# SD.net
KiCad netlist of a schematic drawn in Altium Designer
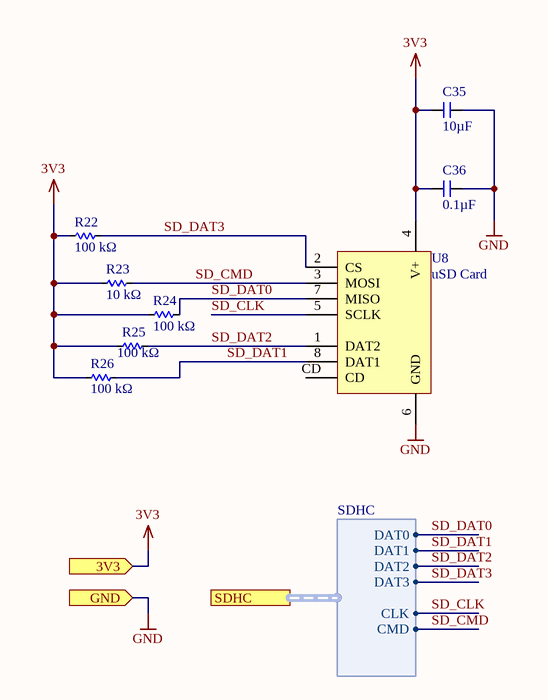
[diagram p0: SD.SchDoc]

(export (version "E")
  (design (tool "Eeschema 10.0.6"))
  (components
    (comp (ref "C35")
      (value "__template_cap")
      (footprint "C0603")
      (description "CAP CER 10UF 35V X5R 0603 20%")
      (fields
        (field (name "CAPACITANCE (SHORTHAND)") "10µF")
        (field (name "MANUFACTURER") "Murata Electronics North America")
      )
      (libsource (lib "passives") (part "__template_cap"))
    )
    (comp (ref "C36")
      (value "__template_cap")
      (footprint "C0603")
      (description "CAP CER 0603 0.1µF X7R 50V 10%")
      (fields
        (field (name "CAPACITANCE (SHORTHAND)") "0.1µF")
        (field (name "MANUFACTURER") "Murata Electronics North America")
      )
      (libsource (lib "passives") (part "__template_cap"))
    )
    (comp (ref "R22")
      (value "__template_resistor")
      (footprint "R0603")
      (description "RES SMD 100K OHM 1% 1/10W 0603")
      (fields
        (field (name "RESISTANCE") "100 kΩ")
        (field (name "MANUFACTURER PART NUMBER") "RC0603FR-07100KL")
        (field (name "MANUFACTURER") "Yageo")
      )
      (libsource (lib "passives") (part "__template_resistor"))
    )
    (comp (ref "R23")
      (value "__template_resistor")
      (footprint "R0603")
      (description "RES SMD 10K OHM 1% 1/10W 0603")
      (fields
        (field (name "RESISTANCE") "10 kΩ")
        (field (name "MANUFACTURER PART NUMBER") "RC0603FR-0710KL")
        (field (name "MANUFACTURER") "Yageo")
      )
      (libsource (lib "passives") (part "__template_resistor"))
    )
    (comp (ref "R24")
      (value "__template_resistor")
      (footprint "R0603")
      (description "RES SMD 100K OHM 1% 1/10W 0603")
      (fields
        (field (name "RESISTANCE") "100 kΩ")
        (field (name "MANUFACTURER PART NUMBER") "RC0603FR-07100KL")
        (field (name "MANUFACTURER") "Yageo")
      )
      (libsource (lib "passives") (part "__template_resistor"))
    )
    (comp (ref "R25")
      (value "__template_resistor")
      (footprint "R0603")
      (description "RES SMD 100K OHM 1% 1/10W 0603")
      (fields
        (field (name "RESISTANCE") "100 kΩ")
        (field (name "MANUFACTURER PART NUMBER") "RC0603FR-07100KL")
        (field (name "MANUFACTURER") "Yageo")
      )
      (libsource (lib "passives") (part "__template_resistor"))
    )
    (comp (ref "R26")
      (value "__template_resistor")
      (footprint "R0603")
      (description "RES SMD 100K OHM 1% 1/10W 0603")
      (fields
        (field (name "RESISTANCE") "100 kΩ")
        (field (name "MANUFACTURER PART NUMBER") "RC0603FR-07100KL")
        (field (name "MANUFACTURER") "Yageo")
      )
      (libsource (lib "passives") (part "__template_resistor"))
    )
    (comp (ref "U8")
      (value "uSD Card")
      (footprint "MICROSD_CARD_SOCKET")
      (description "MICROSD CARD HOLDER, PUSH-PUSH")
      (fields (field (name "MANUFACTURER") "3M") (field (name "MANUFACTURER PART NUMBER") "2908-05WB-MG"))
      (libsource (lib "SSI") (part "MICRO_SD_CARD_HOLDER"))
    )
  )
  (nets
    (net (code "2") (name "/SD_CLK") (class "Default")
      (node (ref "U8") (pin "5") (pinfunction "SCLK_5") (pintype "passive"))
    )
    (net (code "3") (name "/SD_CMD") (class "Default")
      (node (ref "R23") (pin "2") (pintype "passive"))
      (node (ref "U8") (pin "3") (pinfunction "MOSI_3") (pintype "passive"))
    )
    (net (code "4") (name "/SD_DAT0") (class "Default")
      (node (ref "R24") (pin "2") (pintype "passive"))
      (node (ref "U8") (pin "7") (pinfunction "MISO_7") (pintype "passive"))
    )
    (net (code "5") (name "/SD_DAT1") (class "Default")
      (node (ref "R26") (pin "2") (pintype "passive"))
      (node (ref "U8") (pin "8") (pinfunction "DAT1_8") (pintype "passive"))
    )
    (net (code "6") (name "/SD_DAT2") (class "Default")
      (node (ref "R25") (pin "2") (pintype "passive"))
      (node (ref "U8") (pin "1") (pinfunction "DAT2_1") (pintype "passive"))
    )
    (net (code "7") (name "/SD_DAT3") (class "Default")
      (node (ref "R22") (pin "2") (pintype "passive"))
      (node (ref "U8") (pin "2") (pinfunction "CS_2") (pintype "passive"))
    )
    (net (code "9") (name "3V3") (class "Default")
      (node (ref "C35") (pin "2") (pintype "passive"))
      (node (ref "C36") (pin "1") (pintype "passive"))
      (node (ref "R22") (pin "1") (pintype "passive"))
      (node (ref "R23") (pin "1") (pintype "passive"))
      (node (ref "R24") (pin "1") (pintype "passive"))
      (node (ref "R25") (pin "1") (pintype "passive"))
      (node (ref "R26") (pin "1") (pintype "passive"))
      (node (ref "U8") (pin "4") (pinfunction "V+_4") (pintype "passive"))
    )
    (net (code "10") (name "GND") (class "Default")
      (node (ref "C35") (pin "1") (pintype "passive"))
      (node (ref "C36") (pin "2") (pintype "passive"))
      (node (ref "U8") (pin "6") (pinfunction "GND_6") (pintype "passive"))
    )
    (net (code "11") (name "unconnected-(U8-PadCD)") (class "Default")
      (node (ref "U8") (pin "CD") (pinfunction "CD_CD") (pintype "passive"))
    )
  )
)
